# OUT.net
KiCad netlist of a schematic drawn in Altium Designer
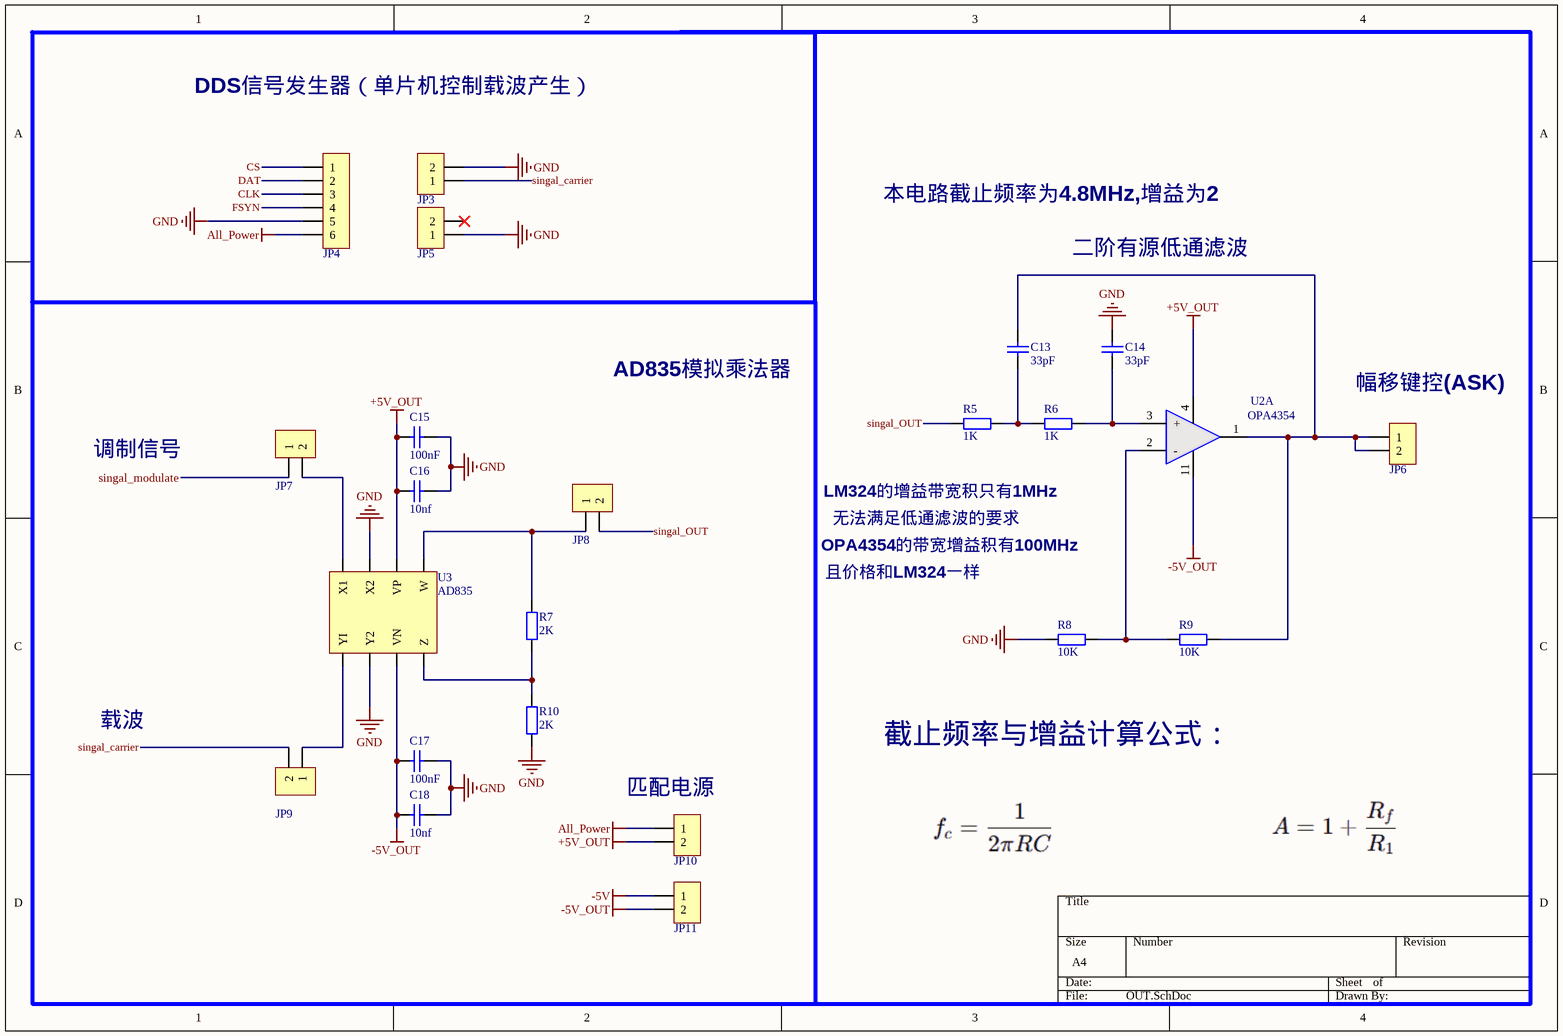
[diagram p0: OUT.SchDoc]

(export (version "E")
  (design (tool "Eeschema 10.0.6"))
  (components
    (comp (ref "C13")
      (value "33pF")
      (footprint "C0603_M")
      (description "贴片电容/MLCC电容")
      (libsource (lib "0.1 - 电阻-电容-电感-保险丝-晶振-晶体-磁珠-电位器-法拉电容-馈通电容") (part "C"))
    )
    (comp (ref "C14")
      (value "33pF")
      (footprint "C0603_M")
      (description "贴片电容/MLCC电容")
      (libsource (lib "0.1 - 电阻-电容-电感-保险丝-晶振-晶体-磁珠-电位器-法拉电容-馈通电容") (part "C"))
    )
    (comp (ref "C15")
      (value "100nF")
      (footprint "C0603_M")
      (description "贴片电容/MLCC电容")
      (libsource (lib "0.1 - 电阻-电容-电感-保险丝-晶振-晶体-磁珠-电位器-法拉电容-馈通电容") (part "C"))
    )
    (comp (ref "C16")
      (value "10nf")
      (footprint "C0603_M")
      (description "贴片电容")
      (libsource (lib "cdud开发板") (part "C_3"))
    )
    (comp (ref "C17")
      (value "100nF")
      (footprint "C0603_M")
      (description "贴片电容/MLCC电容")
      (libsource (lib "0.1 - 电阻-电容-电感-保险丝-晶振-晶体-磁珠-电位器-法拉电容-馈通电容") (part "C"))
    )
    (comp (ref "C18")
      (value "10nf")
      (footprint "C0603_M")
      (description "贴片电容")
      (libsource (lib "cdud开发板") (part "C_3"))
    )
    (comp (ref "JP3")
      (value "HDR-1X2")
      (footprint "HDR2.54-M-LI-2P")
      (description "2P接插件")
      (fields (field (name "版权归属") "封装库来自淘宝 ID：黄晶宝石"))
      (libsource (lib "") (part "Header 2_3"))
    )
    (comp (ref "JP4")
      (value "HDR-1X6")
      (footprint "HDR2.54-M-LI-6P")
      (description "6P接插件")
      (fields (field (name "版权归属") "封装库来自淘宝 ID：黄晶宝石"))
      (libsource (lib "5.4 - 接插件-脚距2.54 (100mil) ") (part "Header 6"))
    )
    (comp (ref "JP5")
      (value "HDR-1X2")
      (footprint "HDR2.54-M-LI-2P")
      (description "2P接插件")
      (fields (field (name "版权归属") "封装库来自淘宝 ID：黄晶宝石"))
      (libsource (lib "") (part "Header 2_3"))
    )
    (comp (ref "JP6")
      (value "HDR-1X2")
      (footprint "HDR2.54-LI-2P")
      (description "2P接插件")
      (fields (field (name "版权归属") "封装库来自淘宝 ID：黄晶宝石"))
      (libsource (lib "") (part "Header 2_1"))
    )
    (comp (ref "JP7")
      (value "HDR-1X2")
      (footprint "HDR2.54-LI-2P")
      (description "2P接插件")
      (fields (field (name "版权归属") "封装库来自淘宝 ID：黄晶宝石"))
      (libsource (lib "5.4 - 接插件-脚距2.54 (100mil) ") (part "Header 2"))
    )
    (comp (ref "JP8")
      (value "HDR-1X2")
      (footprint "HDR2.54-LI-2P")
      (description "2P接插件")
      (fields (field (name "版权归属") "封装库来自淘宝 ID：黄晶宝石"))
      (libsource (lib "5.4 - 接插件-脚距2.54 (100mil) ") (part "Header 2"))
    )
    (comp (ref "JP9")
      (value "HDR-1X2")
      (footprint "HDR2.54-LI-2P")
      (description "2P接插件")
      (fields (field (name "版权归属") "封装库来自淘宝 ID：黄晶宝石"))
      (libsource (lib "") (part "Header 2_2"))
    )
    (comp (ref "JP10")
      (value "HDR-1X2")
      (footprint "HDR2.54-LI-2P")
      (description "2P接插件")
      (libsource (lib "5.5 - 2.54mm连接器(KF2EDGK_XH2.54_2.54排针排母)") (part "Header 2"))
    )
    (comp (ref "JP11")
      (value "HDR-1X2")
      (footprint "HDR2.54-LI-2P")
      (description "2P接插件")
      (libsource (lib "5.5 - 2.54mm连接器(KF2EDGK_XH2.54_2.54排针排母)") (part "Header 2"))
    )
    (comp (ref "R5")
      (value "1K")
      (footprint "R0603_M")
      (description "贴片电阻")
      (libsource (lib "0.1 - 电阻-电容-电感-保险丝-晶振-晶体-磁珠-电位器-法拉电容-馈通电容") (part "R"))
    )
    (comp (ref "R6")
      (value "1K")
      (footprint "R0603_M")
      (description "贴片电阻")
      (libsource (lib "0.1 - 电阻-电容-电感-保险丝-晶振-晶体-磁珠-电位器-法拉电容-馈通电容") (part "R"))
    )
    (comp (ref "R7")
      (value "2K")
      (footprint "R0603_M")
      (description "贴片电阻")
      (libsource (lib "0.1 - 电阻-电容-电感-保险丝-晶振-晶体-磁珠-电位器-法拉电容-馈通电容") (part "R"))
    )
    (comp (ref "R8")
      (value "10K")
      (footprint "R0603_M")
      (description "贴片电阻")
      (libsource (lib "0.1 - 电阻-电容-电感-保险丝-晶振-晶体-磁珠-电位器-法拉电容-馈通电容") (part "R"))
    )
    (comp (ref "R9")
      (value "10K")
      (footprint "R0603_M")
      (description "贴片电阻")
      (libsource (lib "0.1 - 电阻-电容-电感-保险丝-晶振-晶体-磁珠-电位器-法拉电容-馈通电容") (part "R"))
    )
    (comp (ref "R10")
      (value "2K")
      (footprint "R0603_M")
      (description "贴片电阻")
      (libsource (lib "0.1 - 电阻-电容-电感-保险丝-晶振-晶体-磁珠-电位器-法拉电容-馈通电容") (part "R"))
    )
    (comp (ref "U2")
      (value "OPA4354")
      (footprint "SOP14_M")
      (description "4运放")
      (libsource (lib "1.0 - 常见芯片") (part "LM324"))
    )
    (comp (ref "U3")
      (value "AD835")
      (footprint "SOP8_L")
      (description "四象限模拟乘法器")
      (libsource (lib "mylibrary") (part "AD835ARZ"))
    )
  )
  (nets
    (net (code "1") (name "+5V_OUT") (class "Default")
      (node (ref "C15") (pin "1") (pinfunction "1_1") (pintype "passive"))
      (node (ref "C16") (pin "2") (pinfunction "2_2") (pintype "passive"))
      (node (ref "JP10") (pin "2") (pinfunction "2_2") (pintype "passive"))
      (node (ref "U2") (pin "4") (pinfunction "V+_4") (pintype "passive"))
      (node (ref "U3") (pin "6") (pinfunction "VP_6") (pintype "passive"))
    )
    (net (code "2") (name "-5V") (class "Default")
      (node (ref "JP11") (pin "1") (pinfunction "1_1") (pintype "passive"))
    )
    (net (code "3") (name "-5V_OUT") (class "Default")
      (node (ref "C17") (pin "1") (pinfunction "1_1") (pintype "passive"))
      (node (ref "C18") (pin "2") (pinfunction "2_2") (pintype "passive"))
      (node (ref "JP11") (pin "2") (pinfunction "2_2") (pintype "passive"))
      (node (ref "U2") (pin "11") (pinfunction "V-_11") (pintype "passive"))
      (node (ref "U3") (pin "3") (pinfunction "VN_3") (pintype "passive"))
    )
    (net (code "4") (name "/CLK") (class "Default")
      (node (ref "JP4") (pin "3") (pinfunction "3_3") (pintype "passive"))
    )
    (net (code "5") (name "/CS") (class "Default")
      (node (ref "JP4") (pin "1") (pinfunction "1_1") (pintype "passive"))
    )
    (net (code "6") (name "/DAT") (class "Default")
      (node (ref "JP4") (pin "2") (pinfunction "2_2") (pintype "passive"))
    )
    (net (code "7") (name "/FSYN") (class "Default")
      (node (ref "JP4") (pin "4") (pinfunction "4_4") (pintype "passive"))
    )
    (net (code "8") (name "/singal_OUT") (class "Default")
      (node (ref "JP8") (pin "2") (pinfunction "2_2") (pintype "passive"))
      (node (ref "R5") (pin "1") (pinfunction "1_1") (pintype "passive"))
    )
    (net (code "9") (name "/singal_carrier") (class "Default")
      (node (ref "JP3") (pin "1") (pinfunction "1_1") (pintype "passive"))
      (node (ref "JP9") (pin "2") (pinfunction "2_2") (pintype "passive"))
    )
    (net (code "10") (name "/singal_modulate") (class "Default")
      (node (ref "JP7") (pin "1") (pinfunction "1_1") (pintype "passive"))
    )
    (net (code "11") (name "All_Power") (class "Default")
      (node (ref "JP10") (pin "1") (pinfunction "1_1") (pintype "passive"))
      (node (ref "JP4") (pin "6") (pinfunction "6_6") (pintype "passive"))
    )
    (net (code "12") (name "GND") (class "Default")
      (node (ref "C14") (pin "2") (pinfunction "2_2") (pintype "passive"))
      (node (ref "C15") (pin "2") (pinfunction "2_2") (pintype "passive"))
      (node (ref "C16") (pin "1") (pinfunction "1_1") (pintype "passive"))
      (node (ref "C17") (pin "2") (pinfunction "2_2") (pintype "passive"))
      (node (ref "C18") (pin "1") (pinfunction "1_1") (pintype "passive"))
      (node (ref "JP3") (pin "2") (pinfunction "2_2") (pintype "passive"))
      (node (ref "JP4") (pin "5") (pinfunction "5_5") (pintype "passive"))
      (node (ref "JP5") (pin "1") (pinfunction "1_1") (pintype "passive"))
      (node (ref "R10") (pin "1") (pinfunction "1_1") (pintype "passive"))
      (node (ref "R8") (pin "2") (pinfunction "2_2") (pintype "passive"))
      (node (ref "U3") (pin "2") (pinfunction "Y2_2") (pintype "passive"))
      (node (ref "U3") (pin "7") (pinfunction "X2_7") (pintype "passive"))
    )
    (net (code "13") (name "Net-(C13-Pad1)") (class "Default")
      (node (ref "C13") (pin "1") (pinfunction "1_1") (pintype "passive"))
      (node (ref "R5") (pin "2") (pinfunction "2_2") (pintype "passive"))
      (node (ref "R6") (pin "1") (pinfunction "1_1") (pintype "passive"))
    )
    (net (code "14") (name "Net-(U2A-+)") (class "Default")
      (node (ref "C14") (pin "1") (pinfunction "1_1") (pintype "passive"))
      (node (ref "R6") (pin "2") (pinfunction "2_2") (pintype "passive"))
      (node (ref "U2") (pin "3") (pinfunction "+_3") (pintype "passive"))
    )
    (net (code "15") (name "Net-(U2A--)") (class "Default")
      (node (ref "R8") (pin "1") (pinfunction "1_1") (pintype "passive"))
      (node (ref "R9") (pin "1") (pinfunction "1_1") (pintype "passive"))
      (node (ref "U2") (pin "2") (pinfunction "-_2") (pintype "passive"))
    )
    (net (code "16") (name "Net-(U2A-OUT)") (class "Default")
      (node (ref "C13") (pin "2") (pinfunction "2_2") (pintype "passive"))
      (node (ref "JP6") (pin "1") (pinfunction "1_1") (pintype "passive"))
      (node (ref "JP6") (pin "2") (pinfunction "2_2") (pintype "passive"))
      (node (ref "R9") (pin "2") (pinfunction "2_2") (pintype "passive"))
      (node (ref "U2") (pin "1") (pinfunction "OUT_1") (pintype "passive"))
    )
    (net (code "17") (name "Net-(U3-W)") (class "Default")
      (node (ref "JP8") (pin "1") (pinfunction "1_1") (pintype "passive"))
      (node (ref "R7") (pin "1") (pinfunction "1_1") (pintype "passive"))
      (node (ref "U3") (pin "5") (pinfunction "W_5") (pintype "passive"))
    )
    (net (code "18") (name "Net-(U3-X1)") (class "Default")
      (node (ref "JP7") (pin "2") (pinfunction "2_2") (pintype "passive"))
      (node (ref "U3") (pin "8") (pinfunction "X1_8") (pintype "passive"))
    )
    (net (code "19") (name "Net-(U3-YI)") (class "Default")
      (node (ref "JP9") (pin "1") (pinfunction "1_1") (pintype "passive"))
      (node (ref "U3") (pin "1") (pinfunction "YI_1") (pintype "passive"))
    )
    (net (code "20") (name "Net-(U3-Z)") (class "Default")
      (node (ref "R10") (pin "2") (pinfunction "2_2") (pintype "passive"))
      (node (ref "R7") (pin "2") (pinfunction "2_2") (pintype "passive"))
      (node (ref "U3") (pin "4") (pinfunction "Z_4") (pintype "passive"))
    )
    (net (code "21") (name "unconnected-(JP5-Pad2)") (class "Default")
      (node (ref "JP5") (pin "2") (pinfunction "2_2") (pintype "passive+no_connect"))
    )
  )
)
